# Relay.net
KiCad netlist of a schematic drawn in Altium Designer
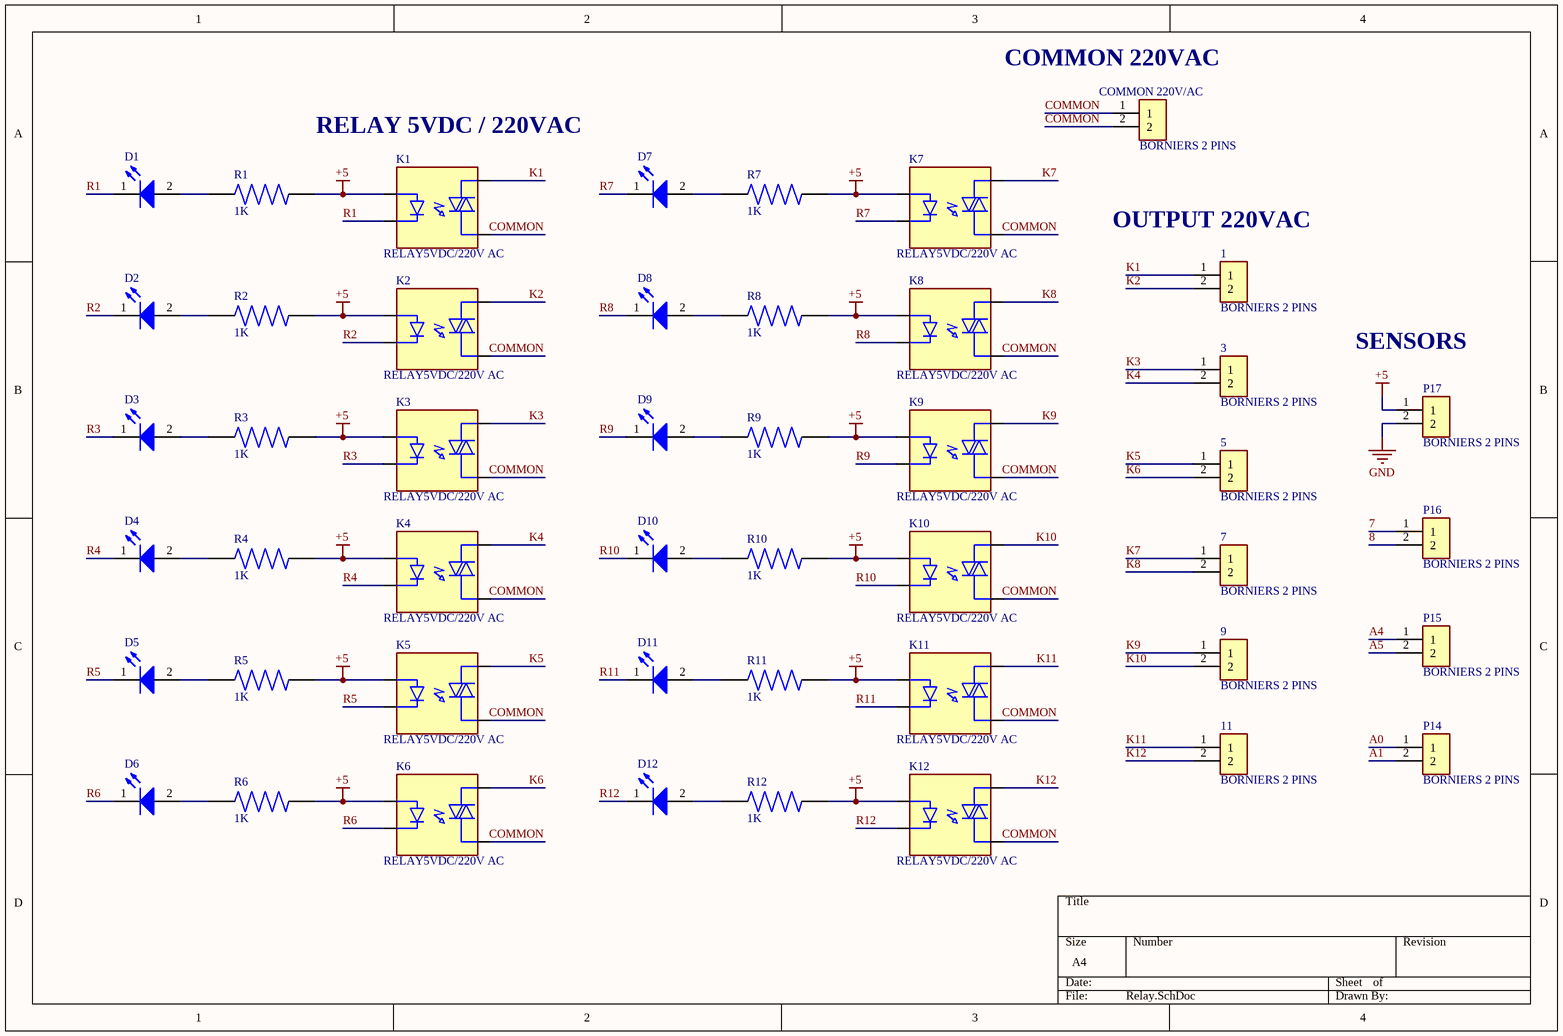
[diagram p0: Relay.SchDoc]

(export (version "E")
  (design (tool "Eeschema 10.0.6"))
  (components
    (comp (ref "1")
      (value "BORNIERS 2 PINS")
      (footprint "BORNIERS 2 PINS")
      (description "Terminal Block Connector Wire Receptacle 2")
      (libsource (lib "Ala Hassine v1.0") (part "BORNIERS 2 PINS"))
    )
    (comp (ref "3")
      (value "BORNIERS 2 PINS")
      (footprint "BORNIERS 2 PINS")
      (description "Terminal Block Connector Wire Receptacle 2")
      (libsource (lib "Ala Hassine v1.0") (part "BORNIERS 2 PINS"))
    )
    (comp (ref "5")
      (value "BORNIERS 2 PINS")
      (footprint "BORNIERS 2 PINS")
      (description "Terminal Block Connector Wire Receptacle 2")
      (libsource (lib "Ala Hassine v1.0") (part "BORNIERS 2 PINS"))
    )
    (comp (ref "7")
      (value "BORNIERS 2 PINS")
      (footprint "BORNIERS 2 PINS")
      (description "Terminal Block Connector Wire Receptacle 2")
      (libsource (lib "Ala Hassine v1.0") (part "BORNIERS 2 PINS"))
    )
    (comp (ref "9")
      (value "BORNIERS 2 PINS")
      (footprint "BORNIERS 2 PINS")
      (description "Terminal Block Connector Wire Receptacle 2")
      (libsource (lib "Ala Hassine v1.0") (part "BORNIERS 2 PINS"))
    )
    (comp (ref "11")
      (value "BORNIERS 2 PINS")
      (footprint "BORNIERS 2 PINS")
      (description "Terminal Block Connector Wire Receptacle 2")
      (libsource (lib "Ala Hassine v1.0") (part "BORNIERS 2 PINS"))
    )
    (comp (ref "COMMON 220V/AC")
      (value "BORNIERS 2 PINS")
      (footprint "BORNIERS 2 PINS")
      (description "Terminal Block Connector Wire Receptacle 2")
      (libsource (lib "Ala Hassine v1.0") (part "BORNIERS 2 PINS"))
    )
    (comp (ref "D1")
      (value "LED 15408085BA400")
      (footprint "LED 15408085BA400")
      (description "SMT Infrared Chip LED Infrared Waterclear, body 2x1.3mm, size 0805, Infrared, 1.4V, 140°")
      (fields
        (field (name "MANUFACTURER PART NUMBER") "15408085BA400")
        (field (name "MANUFACTURER") "Wurth Elektronik")
      )
      (libsource (lib "Ala Hassine v1.0") (part "LED 15408085BA400"))
    )
    (comp (ref "D2")
      (value "LED 15408085BA400")
      (footprint "LED 15408085BA400")
      (description "SMT Infrared Chip LED Infrared Waterclear, body 2x1.3mm, size 0805, Infrared, 1.4V, 140°")
      (fields
        (field (name "MANUFACTURER PART NUMBER") "15408085BA400")
        (field (name "MANUFACTURER") "Wurth Elektronik")
      )
      (libsource (lib "Ala Hassine v1.0") (part "LED 15408085BA400"))
    )
    (comp (ref "D3")
      (value "LED 15408085BA400")
      (footprint "LED 15408085BA400")
      (description "SMT Infrared Chip LED Infrared Waterclear, body 2x1.3mm, size 0805, Infrared, 1.4V, 140°")
      (fields
        (field (name "MANUFACTURER PART NUMBER") "15408085BA400")
        (field (name "MANUFACTURER") "Wurth Elektronik")
      )
      (libsource (lib "Ala Hassine v1.0") (part "LED 15408085BA400"))
    )
    (comp (ref "D4")
      (value "LED 15408085BA400")
      (footprint "LED 15408085BA400")
      (description "SMT Infrared Chip LED Infrared Waterclear, body 2x1.3mm, size 0805, Infrared, 1.4V, 140°")
      (fields
        (field (name "MANUFACTURER PART NUMBER") "15408085BA400")
        (field (name "MANUFACTURER") "Wurth Elektronik")
      )
      (libsource (lib "Ala Hassine v1.0") (part "LED 15408085BA400"))
    )
    (comp (ref "D5")
      (value "LED 15408085BA400")
      (footprint "LED 15408085BA400")
      (description "SMT Infrared Chip LED Infrared Waterclear, body 2x1.3mm, size 0805, Infrared, 1.4V, 140°")
      (fields
        (field (name "MANUFACTURER PART NUMBER") "15408085BA400")
        (field (name "MANUFACTURER") "Wurth Elektronik")
      )
      (libsource (lib "Ala Hassine v1.0") (part "LED 15408085BA400"))
    )
    (comp (ref "D6")
      (value "LED 15408085BA400")
      (footprint "LED 15408085BA400")
      (description "SMT Infrared Chip LED Infrared Waterclear, body 2x1.3mm, size 0805, Infrared, 1.4V, 140°")
      (fields
        (field (name "MANUFACTURER PART NUMBER") "15408085BA400")
        (field (name "MANUFACTURER") "Wurth Elektronik")
      )
      (libsource (lib "Ala Hassine v1.0") (part "LED 15408085BA400"))
    )
    (comp (ref "D7")
      (value "LED 15408085BA400")
      (footprint "LED 15408085BA400")
      (description "SMT Infrared Chip LED Infrared Waterclear, body 2x1.3mm, size 0805, Infrared, 1.4V, 140°")
      (fields
        (field (name "MANUFACTURER PART NUMBER") "15408085BA400")
        (field (name "MANUFACTURER") "Wurth Elektronik")
      )
      (libsource (lib "Ala Hassine v1.0") (part "LED 15408085BA400"))
    )
    (comp (ref "D8")
      (value "LED 15408085BA400")
      (footprint "LED 15408085BA400")
      (description "SMT Infrared Chip LED Infrared Waterclear, body 2x1.3mm, size 0805, Infrared, 1.4V, 140°")
      (fields
        (field (name "MANUFACTURER PART NUMBER") "15408085BA400")
        (field (name "MANUFACTURER") "Wurth Elektronik")
      )
      (libsource (lib "Ala Hassine v1.0") (part "LED 15408085BA400"))
    )
    (comp (ref "D9")
      (value "LED 15408085BA400")
      (footprint "LED 15408085BA400")
      (description "SMT Infrared Chip LED Infrared Waterclear, body 2x1.3mm, size 0805, Infrared, 1.4V, 140°")
      (fields
        (field (name "MANUFACTURER PART NUMBER") "15408085BA400")
        (field (name "MANUFACTURER") "Wurth Elektronik")
      )
      (libsource (lib "Ala Hassine v1.0") (part "LED 15408085BA400"))
    )
    (comp (ref "D10")
      (value "LED 15408085BA400")
      (footprint "LED 15408085BA400")
      (description "SMT Infrared Chip LED Infrared Waterclear, body 2x1.3mm, size 0805, Infrared, 1.4V, 140°")
      (fields
        (field (name "MANUFACTURER PART NUMBER") "15408085BA400")
        (field (name "MANUFACTURER") "Wurth Elektronik")
      )
      (libsource (lib "Ala Hassine v1.0") (part "LED 15408085BA400"))
    )
    (comp (ref "D11")
      (value "LED 15408085BA400")
      (footprint "LED 15408085BA400")
      (description "SMT Infrared Chip LED Infrared Waterclear, body 2x1.3mm, size 0805, Infrared, 1.4V, 140°")
      (fields
        (field (name "MANUFACTURER PART NUMBER") "15408085BA400")
        (field (name "MANUFACTURER") "Wurth Elektronik")
      )
      (libsource (lib "Ala Hassine v1.0") (part "LED 15408085BA400"))
    )
    (comp (ref "D12")
      (value "LED 15408085BA400")
      (footprint "LED 15408085BA400")
      (description "SMT Infrared Chip LED Infrared Waterclear, body 2x1.3mm, size 0805, Infrared, 1.4V, 140°")
      (fields
        (field (name "MANUFACTURER PART NUMBER") "15408085BA400")
        (field (name "MANUFACTURER") "Wurth Elektronik")
      )
      (libsource (lib "Ala Hassine v1.0") (part "LED 15408085BA400"))
    )
    (comp (ref "K1")
      (value "RELAY5VDC/220V AC")
      (footprint "G3MB-202P DC5")
      (description "Solid State Photo-Coupled Relay (PhotoRelay) SPST-NO (1 Form A) 4-SIP")
      (fields (field (name "MF") "Omron Automation") (field (name "MP") "G3MB-202P"))
      (libsource (lib "Ala Hassine v1.0") (part "G3MB-202P DC5"))
    )
    (comp (ref "K2")
      (value "RELAY5VDC/220V AC")
      (footprint "G3MB-202P DC5")
      (description "Solid State Photo-Coupled Relay (PhotoRelay) SPST-NO (1 Form A) 4-SIP")
      (fields (field (name "MF") "Omron Automation") (field (name "MP") "G3MB-202P"))
      (libsource (lib "Ala Hassine v1.0") (part "G3MB-202P DC5"))
    )
    (comp (ref "K3")
      (value "RELAY5VDC/220V AC")
      (footprint "G3MB-202P DC5")
      (description "Solid State Photo-Coupled Relay (PhotoRelay) SPST-NO (1 Form A) 4-SIP")
      (fields (field (name "MF") "Omron Automation") (field (name "MP") "G3MB-202P"))
      (libsource (lib "Ala Hassine v1.0") (part "G3MB-202P DC5"))
    )
    (comp (ref "K4")
      (value "RELAY5VDC/220V AC")
      (footprint "G3MB-202P DC5")
      (description "Solid State Photo-Coupled Relay (PhotoRelay) SPST-NO (1 Form A) 4-SIP")
      (fields (field (name "MF") "Omron Automation") (field (name "MP") "G3MB-202P"))
      (libsource (lib "Ala Hassine v1.0") (part "G3MB-202P DC5"))
    )
    (comp (ref "K5")
      (value "RELAY5VDC/220V AC")
      (footprint "G3MB-202P DC5")
      (description "Solid State Photo-Coupled Relay (PhotoRelay) SPST-NO (1 Form A) 4-SIP")
      (fields (field (name "MF") "Omron Automation") (field (name "MP") "G3MB-202P"))
      (libsource (lib "Ala Hassine v1.0") (part "G3MB-202P DC5"))
    )
    (comp (ref "K6")
      (value "RELAY5VDC/220V AC")
      (footprint "G3MB-202P DC5")
      (description "Solid State Photo-Coupled Relay (PhotoRelay) SPST-NO (1 Form A) 4-SIP")
      (fields (field (name "MF") "Omron Automation") (field (name "MP") "G3MB-202P"))
      (libsource (lib "Ala Hassine v1.0") (part "G3MB-202P DC5"))
    )
    (comp (ref "K7")
      (value "RELAY5VDC/220V AC")
      (footprint "G3MB-202P DC5")
      (description "Solid State Photo-Coupled Relay (PhotoRelay) SPST-NO (1 Form A) 4-SIP")
      (fields (field (name "MF") "Omron Automation") (field (name "MP") "G3MB-202P"))
      (libsource (lib "Ala Hassine v1.0") (part "G3MB-202P DC5"))
    )
    (comp (ref "K8")
      (value "RELAY5VDC/220V AC")
      (footprint "G3MB-202P DC5")
      (description "Solid State Photo-Coupled Relay (PhotoRelay) SPST-NO (1 Form A) 4-SIP")
      (fields (field (name "MF") "Omron Automation") (field (name "MP") "G3MB-202P"))
      (libsource (lib "Ala Hassine v1.0") (part "G3MB-202P DC5"))
    )
    (comp (ref "K9")
      (value "RELAY5VDC/220V AC")
      (footprint "G3MB-202P DC5")
      (description "Solid State Photo-Coupled Relay (PhotoRelay) SPST-NO (1 Form A) 4-SIP")
      (fields (field (name "MF") "Omron Automation") (field (name "MP") "G3MB-202P"))
      (libsource (lib "Ala Hassine v1.0") (part "G3MB-202P DC5"))
    )
    (comp (ref "K10")
      (value "RELAY5VDC/220V AC")
      (footprint "G3MB-202P DC5")
      (description "Solid State Photo-Coupled Relay (PhotoRelay) SPST-NO (1 Form A) 4-SIP")
      (fields (field (name "MF") "Omron Automation") (field (name "MP") "G3MB-202P"))
      (libsource (lib "Ala Hassine v1.0") (part "G3MB-202P DC5"))
    )
    (comp (ref "K11")
      (value "RELAY5VDC/220V AC")
      (footprint "G3MB-202P DC5")
      (description "Solid State Photo-Coupled Relay (PhotoRelay) SPST-NO (1 Form A) 4-SIP")
      (fields (field (name "MF") "Omron Automation") (field (name "MP") "G3MB-202P"))
      (libsource (lib "Ala Hassine v1.0") (part "G3MB-202P DC5"))
    )
    (comp (ref "K12")
      (value "RELAY5VDC/220V AC")
      (footprint "G3MB-202P DC5")
      (description "Solid State Photo-Coupled Relay (PhotoRelay) SPST-NO (1 Form A) 4-SIP")
      (fields (field (name "MF") "Omron Automation") (field (name "MP") "G3MB-202P"))
      (libsource (lib "Ala Hassine v1.0") (part "G3MB-202P DC5"))
    )
    (comp (ref "P14")
      (value "BORNIERS 2 PINS")
      (footprint "BORNIERS 2 PINS")
      (description "Terminal Block Connector Wire Receptacle 2")
      (libsource (lib "Ala Hassine v1.0") (part "BORNIERS 2 PINS"))
    )
    (comp (ref "P15")
      (value "BORNIERS 2 PINS")
      (footprint "BORNIERS 2 PINS")
      (description "Terminal Block Connector Wire Receptacle 2")
      (libsource (lib "Ala Hassine v1.0") (part "BORNIERS 2 PINS"))
    )
    (comp (ref "P16")
      (value "BORNIERS 2 PINS")
      (footprint "BORNIERS 2 PINS")
      (description "Terminal Block Connector Wire Receptacle 2")
      (libsource (lib "Ala Hassine v1.0") (part "BORNIERS 2 PINS"))
    )
    (comp (ref "P17")
      (value "BORNIERS 2 PINS")
      (footprint "BORNIERS 2 PINS")
      (description "Terminal Block Connector Wire Receptacle 2")
      (libsource (lib "Ala Hassine v1.0") (part "BORNIERS 2 PINS"))
    )
    (comp (ref "R1")
      (value "1K")
      (footprint "RES FCR1206J10R")
      (description "RES 1206 10 Ohm 5% 1/8W ±500ppm/°C Molded SMD SMD T/R")
      (fields (field (name "TOLERANCE") "5%") (field (name "MP") "FCR1206J10R"))
      (libsource (lib "Ala Hassine v1.0") (part "RES FCR1206J10R"))
    )
    (comp (ref "R2")
      (value "1K")
      (footprint "RES FCR1206J10R")
      (description "RES 1206 10 Ohm 5% 1/8W ±500ppm/°C Molded SMD SMD T/R")
      (fields (field (name "TOLERANCE") "5%") (field (name "MP") "FCR1206J10R"))
      (libsource (lib "Ala Hassine v1.0") (part "RES FCR1206J10R"))
    )
    (comp (ref "R3")
      (value "1K")
      (footprint "RES FCR1206J10R")
      (description "RES 1206 10 Ohm 5% 1/8W ±500ppm/°C Molded SMD SMD T/R")
      (fields (field (name "TOLERANCE") "5%") (field (name "MP") "FCR1206J10R"))
      (libsource (lib "Ala Hassine v1.0") (part "RES FCR1206J10R"))
    )
    (comp (ref "R4")
      (value "1K")
      (footprint "RES FCR1206J10R")
      (description "RES 1206 10 Ohm 5% 1/8W ±500ppm/°C Molded SMD SMD T/R")
      (fields (field (name "TOLERANCE") "5%") (field (name "MP") "FCR1206J10R"))
      (libsource (lib "Ala Hassine v1.0") (part "RES FCR1206J10R"))
    )
    (comp (ref "R5")
      (value "1K")
      (footprint "RES FCR1206J10R")
      (description "RES 1206 10 Ohm 5% 1/8W ±500ppm/°C Molded SMD SMD T/R")
      (fields (field (name "TOLERANCE") "5%") (field (name "MP") "FCR1206J10R"))
      (libsource (lib "Ala Hassine v1.0") (part "RES FCR1206J10R"))
    )
    (comp (ref "R6")
      (value "1K")
      (footprint "RES FCR1206J10R")
      (description "RES 1206 10 Ohm 5% 1/8W ±500ppm/°C Molded SMD SMD T/R")
      (fields (field (name "TOLERANCE") "5%") (field (name "MP") "FCR1206J10R"))
      (libsource (lib "Ala Hassine v1.0") (part "RES FCR1206J10R"))
    )
    (comp (ref "R7")
      (value "1K")
      (footprint "RES FCR1206J10R")
      (description "RES 1206 10 Ohm 5% 1/8W ±500ppm/°C Molded SMD SMD T/R")
      (fields (field (name "TOLERANCE") "5%") (field (name "MP") "FCR1206J10R"))
      (libsource (lib "Ala Hassine v1.0") (part "RES FCR1206J10R"))
    )
    (comp (ref "R8")
      (value "1K")
      (footprint "RES FCR1206J10R")
      (description "RES 1206 10 Ohm 5% 1/8W ±500ppm/°C Molded SMD SMD T/R")
      (fields (field (name "TOLERANCE") "5%") (field (name "MP") "FCR1206J10R"))
      (libsource (lib "Ala Hassine v1.0") (part "RES FCR1206J10R"))
    )
    (comp (ref "R9")
      (value "1K")
      (footprint "RES FCR1206J10R")
      (description "RES 1206 10 Ohm 5% 1/8W ±500ppm/°C Molded SMD SMD T/R")
      (fields (field (name "TOLERANCE") "5%") (field (name "MP") "FCR1206J10R"))
      (libsource (lib "Ala Hassine v1.0") (part "RES FCR1206J10R"))
    )
    (comp (ref "R10")
      (value "1K")
      (footprint "RES FCR1206J10R")
      (description "RES 1206 10 Ohm 5% 1/8W ±500ppm/°C Molded SMD SMD T/R")
      (fields (field (name "TOLERANCE") "5%") (field (name "MP") "FCR1206J10R"))
      (libsource (lib "Ala Hassine v1.0") (part "RES FCR1206J10R"))
    )
    (comp (ref "R11")
      (value "1K")
      (footprint "RES FCR1206J10R")
      (description "RES 1206 10 Ohm 5% 1/8W ±500ppm/°C Molded SMD SMD T/R")
      (fields (field (name "TOLERANCE") "5%") (field (name "MP") "FCR1206J10R"))
      (libsource (lib "Ala Hassine v1.0") (part "RES FCR1206J10R"))
    )
    (comp (ref "R12")
      (value "1K")
      (footprint "RES FCR1206J10R")
      (description "RES 1206 10 Ohm 5% 1/8W ±500ppm/°C Molded SMD SMD T/R")
      (fields (field (name "TOLERANCE") "5%") (field (name "MP") "FCR1206J10R"))
      (libsource (lib "Ala Hassine v1.0") (part "RES FCR1206J10R"))
    )
  )
  (nets
    (net (code "1") (name "+5") (class "Default")
      (node (ref "K1") (pin "3") (pinfunction "ANODE_3") (pintype "passive"))
      (node (ref "K10") (pin "3") (pinfunction "ANODE_3") (pintype "passive"))
      (node (ref "K11") (pin "3") (pinfunction "ANODE_3") (pintype "passive"))
      (node (ref "K12") (pin "3") (pinfunction "ANODE_3") (pintype "passive"))
      (node (ref "K2") (pin "3") (pinfunction "ANODE_3") (pintype "passive"))
      (node (ref "K3") (pin "3") (pinfunction "ANODE_3") (pintype "passive"))
      (node (ref "K4") (pin "3") (pinfunction "ANODE_3") (pintype "passive"))
      (node (ref "K5") (pin "3") (pinfunction "ANODE_3") (pintype "passive"))
      (node (ref "K6") (pin "3") (pinfunction "ANODE_3") (pintype "passive"))
      (node (ref "K7") (pin "3") (pinfunction "ANODE_3") (pintype "passive"))
      (node (ref "K8") (pin "3") (pinfunction "ANODE_3") (pintype "passive"))
      (node (ref "K9") (pin "3") (pinfunction "ANODE_3") (pintype "passive"))
      (node (ref "P17") (pin "1") (pinfunction "1_1") (pintype "passive"))
      (node (ref "R1") (pin "2") (pinfunction "2_2") (pintype "passive"))
      (node (ref "R10") (pin "2") (pinfunction "2_2") (pintype "passive"))
      (node (ref "R11") (pin "2") (pinfunction "2_2") (pintype "passive"))
      (node (ref "R12") (pin "2") (pinfunction "2_2") (pintype "passive"))
      (node (ref "R2") (pin "2") (pinfunction "2_2") (pintype "passive"))
      (node (ref "R3") (pin "2") (pinfunction "2_2") (pintype "passive"))
      (node (ref "R4") (pin "2") (pinfunction "2_2") (pintype "passive"))
      (node (ref "R5") (pin "2") (pinfunction "2_2") (pintype "passive"))
      (node (ref "R6") (pin "2") (pinfunction "2_2") (pintype "passive"))
      (node (ref "R7") (pin "2") (pinfunction "2_2") (pintype "passive"))
      (node (ref "R8") (pin "2") (pinfunction "2_2") (pintype "passive"))
      (node (ref "R9") (pin "2") (pinfunction "2_2") (pintype "passive"))
    )
    (net (code "2") (name "/7") (class "Default")
      (node (ref "P16") (pin "1") (pinfunction "1_1") (pintype "passive"))
    )
    (net (code "3") (name "/8") (class "Default")
      (node (ref "P16") (pin "2") (pinfunction "2_2") (pintype "passive"))
    )
    (net (code "4") (name "/A0") (class "Default")
      (node (ref "P14") (pin "1") (pinfunction "1_1") (pintype "passive"))
    )
    (net (code "5") (name "/A1") (class "Default")
      (node (ref "P14") (pin "2") (pinfunction "2_2") (pintype "passive"))
    )
    (net (code "6") (name "/A4") (class "Default")
      (node (ref "P15") (pin "1") (pinfunction "1_1") (pintype "passive"))
    )
    (net (code "7") (name "/A5") (class "Default")
      (node (ref "P15") (pin "2") (pinfunction "2_2") (pintype "passive"))
    )
    (net (code "8") (name "/COMMON") (class "Default")
      (node (ref "COMMON 220V/AC") (pin "1") (pinfunction "1_1") (pintype "passive"))
      (node (ref "COMMON 220V/AC") (pin "2") (pinfunction "2_2") (pintype "passive"))
      (node (ref "K1") (pin "2") (pinfunction "LOAD2_2") (pintype "passive"))
      (node (ref "K10") (pin "2") (pinfunction "LOAD2_2") (pintype "passive"))
      (node (ref "K11") (pin "2") (pinfunction "LOAD2_2") (pintype "passive"))
      (node (ref "K12") (pin "2") (pinfunction "LOAD2_2") (pintype "passive"))
      (node (ref "K2") (pin "2") (pinfunction "LOAD2_2") (pintype "passive"))
      (node (ref "K3") (pin "2") (pinfunction "LOAD2_2") (pintype "passive"))
      (node (ref "K4") (pin "2") (pinfunction "LOAD2_2") (pintype "passive"))
      (node (ref "K5") (pin "2") (pinfunction "LOAD2_2") (pintype "passive"))
      (node (ref "K6") (pin "2") (pinfunction "LOAD2_2") (pintype "passive"))
      (node (ref "K7") (pin "2") (pinfunction "LOAD2_2") (pintype "passive"))
      (node (ref "K8") (pin "2") (pinfunction "LOAD2_2") (pintype "passive"))
      (node (ref "K9") (pin "2") (pinfunction "LOAD2_2") (pintype "passive"))
    )
    (net (code "9") (name "/K1") (class "Default")
      (node (ref "1") (pin "1") (pinfunction "1_1") (pintype "passive"))
      (node (ref "K1") (pin "1") (pinfunction "LOAD1_1") (pintype "passive"))
    )
    (net (code "10") (name "/K2") (class "Default")
      (node (ref "1") (pin "2") (pinfunction "2_2") (pintype "passive"))
      (node (ref "K2") (pin "1") (pinfunction "LOAD1_1") (pintype "passive"))
    )
    (net (code "11") (name "/K3") (class "Default")
      (node (ref "3") (pin "1") (pinfunction "1_1") (pintype "passive"))
      (node (ref "K3") (pin "1") (pinfunction "LOAD1_1") (pintype "passive"))
    )
    (net (code "12") (name "/K4") (class "Default")
      (node (ref "3") (pin "2") (pinfunction "2_2") (pintype "passive"))
      (node (ref "K4") (pin "1") (pinfunction "LOAD1_1") (pintype "passive"))
    )
    (net (code "13") (name "/K5") (class "Default")
      (node (ref "5") (pin "1") (pinfunction "1_1") (pintype "passive"))
      (node (ref "K5") (pin "1") (pinfunction "LOAD1_1") (pintype "passive"))
    )
    (net (code "14") (name "/K6") (class "Default")
      (node (ref "5") (pin "2") (pinfunction "2_2") (pintype "passive"))
      (node (ref "K6") (pin "1") (pinfunction "LOAD1_1") (pintype "passive"))
    )
    (net (code "15") (name "/K7") (class "Default")
      (node (ref "7") (pin "1") (pinfunction "1_1") (pintype "passive"))
      (node (ref "K7") (pin "1") (pinfunction "LOAD1_1") (pintype "passive"))
    )
    (net (code "16") (name "/K8") (class "Default")
      (node (ref "7") (pin "2") (pinfunction "2_2") (pintype "passive"))
      (node (ref "K8") (pin "1") (pinfunction "LOAD1_1") (pintype "passive"))
    )
    (net (code "17") (name "/K9") (class "Default")
      (node (ref "9") (pin "1") (pinfunction "1_1") (pintype "passive"))
      (node (ref "K9") (pin "1") (pinfunction "LOAD1_1") (pintype "passive"))
    )
    (net (code "18") (name "/K10") (class "Default")
      (node (ref "9") (pin "2") (pinfunction "2_2") (pintype "passive"))
      (node (ref "K10") (pin "1") (pinfunction "LOAD1_1") (pintype "passive"))
    )
    (net (code "19") (name "/K11") (class "Default")
      (node (ref "11") (pin "1") (pinfunction "1_1") (pintype "passive"))
      (node (ref "K11") (pin "1") (pinfunction "LOAD1_1") (pintype "passive"))
    )
    (net (code "20") (name "/K12") (class "Default")
      (node (ref "11") (pin "2") (pinfunction "2_2") (pintype "passive"))
      (node (ref "K12") (pin "1") (pinfunction "LOAD1_1") (pintype "passive"))
    )
    (net (code "21") (name "/R1") (class "Default")
      (node (ref "D1") (pin "1") (pinfunction "K_1") (pintype "passive"))
      (node (ref "K1") (pin "4") (pinfunction "CATHODE_4") (pintype "passive"))
    )
    (net (code "22") (name "/R2") (class "Default")
      (node (ref "D2") (pin "1") (pinfunction "K_1") (pintype "passive"))
      (node (ref "K2") (pin "4") (pinfunction "CATHODE_4") (pintype "passive"))
    )
    (net (code "23") (name "/R3") (class "Default")
      (node (ref "D3") (pin "1") (pinfunction "K_1") (pintype "passive"))
      (node (ref "K3") (pin "4") (pinfunction "CATHODE_4") (pintype "passive"))
    )
    (net (code "24") (name "/R4") (class "Default")
      (node (ref "D4") (pin "1") (pinfunction "K_1") (pintype "passive"))
      (node (ref "K4") (pin "4") (pinfunction "CATHODE_4") (pintype "passive"))
    )
    (net (code "25") (name "/R5") (class "Default")
      (node (ref "D5") (pin "1") (pinfunction "K_1") (pintype "passive"))
      (node (ref "K5") (pin "4") (pinfunction "CATHODE_4") (pintype "passive"))
    )
    (net (code "26") (name "/R6") (class "Default")
      (node (ref "D6") (pin "1") (pinfunction "K_1") (pintype "passive"))
      (node (ref "K6") (pin "4") (pinfunction "CATHODE_4") (pintype "passive"))
    )
    (net (code "27") (name "/R7") (class "Default")
      (node (ref "D7") (pin "1") (pinfunction "K_1") (pintype "passive"))
      (node (ref "K7") (pin "4") (pinfunction "CATHODE_4") (pintype "passive"))
    )
    (net (code "28") (name "/R8") (class "Default")
      (node (ref "D8") (pin "1") (pinfunction "K_1") (pintype "passive"))
      (node (ref "K8") (pin "4") (pinfunction "CATHODE_4") (pintype "passive"))
    )
    (net (code "29") (name "/R9") (class "Default")
      (node (ref "D9") (pin "1") (pinfunction "K_1") (pintype "passive"))
      (node (ref "K9") (pin "4") (pinfunction "CATHODE_4") (pintype "passive"))
    )
    (net (code "30") (name "/R10") (class "Default")
      (node (ref "D10") (pin "1") (pinfunction "K_1") (pintype "passive"))
      (node (ref "K10") (pin "4") (pinfunction "CATHODE_4") (pintype "passive"))
    )
    (net (code "31") (name "/R11") (class "Default")
      (node (ref "D11") (pin "1") (pinfunction "K_1") (pintype "passive"))
      (node (ref "K11") (pin "4") (pinfunction "CATHODE_4") (pintype "passive"))
    )
    (net (code "32") (name "/R12") (class "Default")
      (node (ref "D12") (pin "1") (pinfunction "K_1") (pintype "passive"))
      (node (ref "K12") (pin "4") (pinfunction "CATHODE_4") (pintype "passive"))
    )
    (net (code "33") (name "GND") (class "Default")
      (node (ref "P17") (pin "2") (pinfunction "2_2") (pintype "passive"))
    )
    (net (code "34") (name "Net-(D1-A)") (class "Default")
      (node (ref "D1") (pin "2") (pinfunction "A_2") (pintype "passive"))
      (node (ref "R1") (pin "1") (pinfunction "1_1") (pintype "passive"))
    )
    (net (code "35") (name "Net-(D2-A)") (class "Default")
      (node (ref "D2") (pin "2") (pinfunction "A_2") (pintype "passive"))
      (node (ref "R2") (pin "1") (pinfunction "1_1") (pintype "passive"))
    )
    (net (code "36") (name "Net-(D3-A)") (class "Default")
      (node (ref "D3") (pin "2") (pinfunction "A_2") (pintype "passive"))
      (node (ref "R3") (pin "1") (pinfunction "1_1") (pintype "passive"))
    )
    (net (code "37") (name "Net-(D4-A)") (class "Default")
      (node (ref "D4") (pin "2") (pinfunction "A_2") (pintype "passive"))
      (node (ref "R4") (pin "1") (pinfunction "1_1") (pintype "passive"))
    )
    (net (code "38") (name "Net-(D5-A)") (class "Default")
      (node (ref "D5") (pin "2") (pinfunction "A_2") (pintype "passive"))
      (node (ref "R5") (pin "1") (pinfunction "1_1") (pintype "passive"))
    )
    (net (code "39") (name "Net-(D6-A)") (class "Default")
      (node (ref "D6") (pin "2") (pinfunction "A_2") (pintype "passive"))
      (node (ref "R6") (pin "1") (pinfunction "1_1") (pintype "passive"))
    )
    (net (code "40") (name "Net-(D7-A)") (class "Default")
      (node (ref "D7") (pin "2") (pinfunction "A_2") (pintype "passive"))
      (node (ref "R7") (pin "1") (pinfunction "1_1") (pintype "passive"))
    )
    (net (code "41") (name "Net-(D8-A)") (class "Default")
      (node (ref "D8") (pin "2") (pinfunction "A_2") (pintype "passive"))
      (node (ref "R8") (pin "1") (pinfunction "1_1") (pintype "passive"))
    )
    (net (code "42") (name "Net-(D9-A)") (class "Default")
      (node (ref "D9") (pin "2") (pinfunction "A_2") (pintype "passive"))
      (node (ref "R9") (pin "1") (pinfunction "1_1") (pintype "passive"))
    )
    (net (code "43") (name "Net-(D10-A)") (class "Default")
      (node (ref "D10") (pin "2") (pinfunction "A_2") (pintype "passive"))
      (node (ref "R10") (pin "1") (pinfunction "1_1") (pintype "passive"))
    )
    (net (code "44") (name "Net-(D11-A)") (class "Default")
      (node (ref "D11") (pin "2") (pinfunction "A_2") (pintype "passive"))
      (node (ref "R11") (pin "1") (pinfunction "1_1") (pintype "passive"))
    )
    (net (code "45") (name "Net-(D12-A)") (class "Default")
      (node (ref "D12") (pin "2") (pinfunction "A_2") (pintype "passive"))
      (node (ref "R12") (pin "1") (pinfunction "1_1") (pintype "passive"))
    )
  )
)
